# dianzicheng.net
KiCad netlist of a schematic drawn in Altium Designer
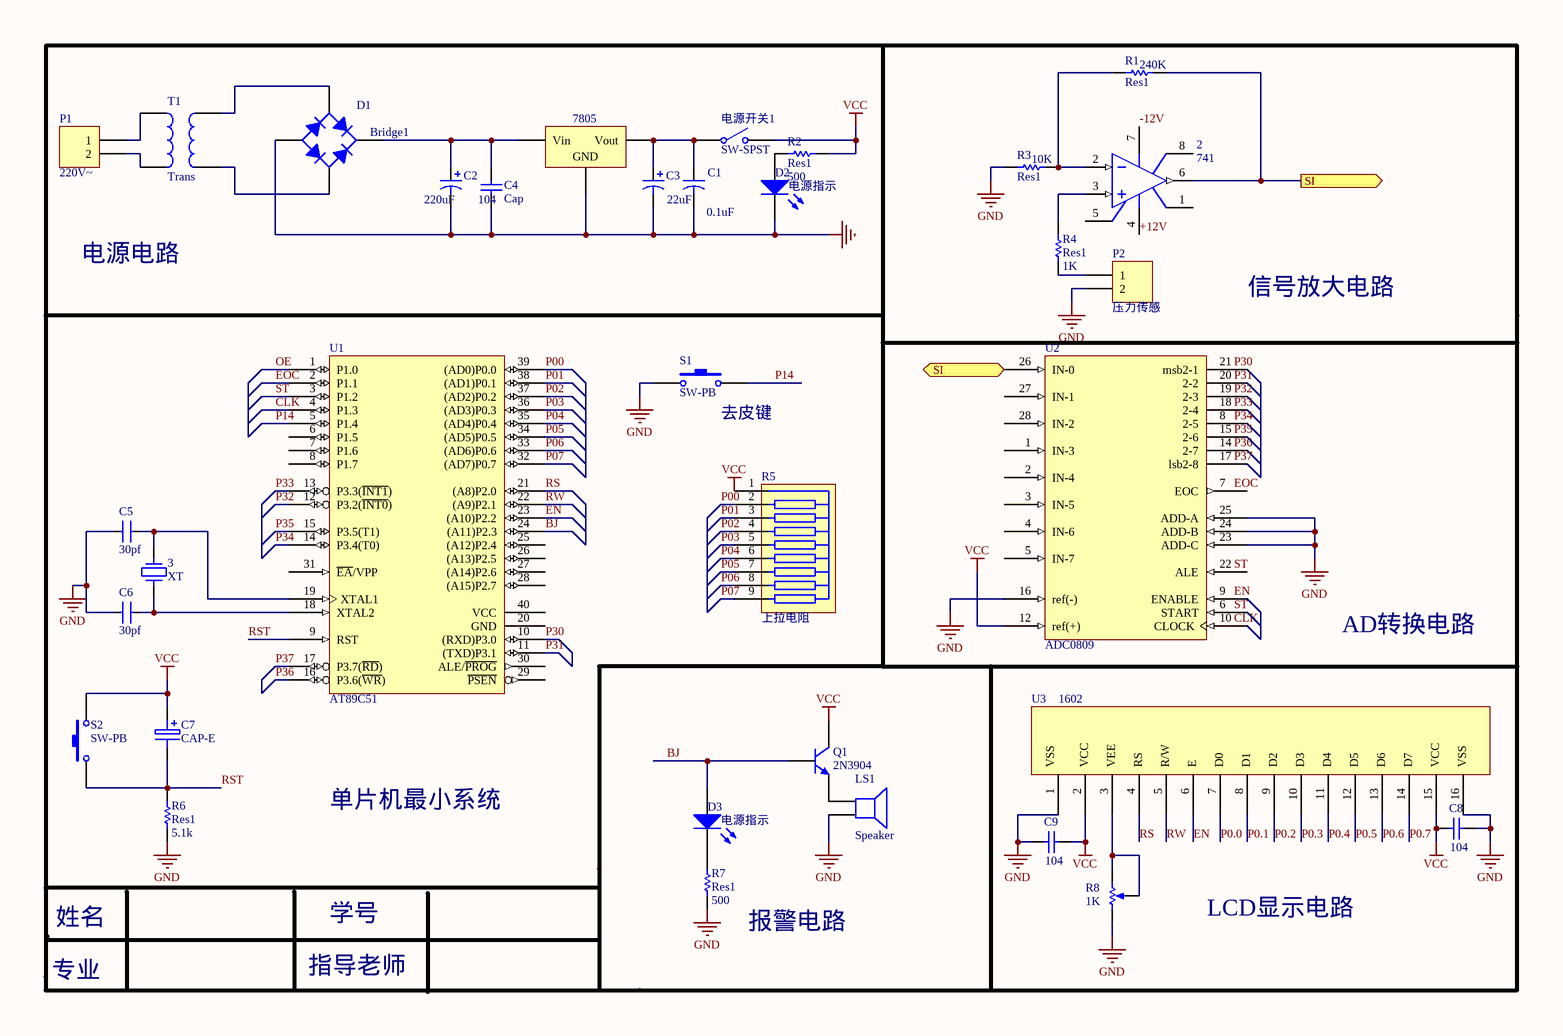
[diagram p0: dianzicheng.SchDoc]

(export (version "E")
  (design (tool "Eeschema 10.0.6"))
  (components
    (comp (ref "2")
      (value "741")
      (footprint "H-08A")
      (description "FET Operational Amplifier")
      (fields (field (name "PUBLISHER") "Altium Limited"))
      (libsource (lib "Miscellaneous Devices") (part "Op Amp"))
    )
    (comp (ref "3") (value "XT") (footprint "HC-49S") (description "晶振") (libsource (lib "常用器件") (part "XT")))
    (comp (ref "7805")
      (value "~")
      (footprint "SIP-G3/Y2")
      (description "Voltage Regulator")
      (fields (field (name "PUBLISHER") "Altium Limited"))
      (libsource (lib "Miscellaneous Devices") (part "Volt Reg"))
    )
    (comp (ref "C1")
      (value "0.1uF")
      (footprint "CAPR5-4X5")
      (description "Capacitor")
      (fields (field (name "PUBLISHER") "Altium Limited"))
      (libsource (lib "Miscellaneous Devices") (part "Cap2"))
    )
    (comp (ref "C2")
      (value "220uF")
      (footprint "CC2012-0805")
      (description "Polarized Capacitor (Surface Mount)")
      (fields (field (name "PUBLISHER") "Altium Limited"))
      (libsource (lib "Miscellaneous Devices") (part "Cap Pol3"))
    )
    (comp (ref "C3")
      (value "22uF")
      (footprint "CC2012-0805")
      (description "Polarized Capacitor (Surface Mount)")
      (fields (field (name "PUBLISHER") "Altium Limited"))
      (libsource (lib "Miscellaneous Devices") (part "Cap Pol3"))
    )
    (comp (ref "C4")
      (value "Cap")
      (footprint "RAD-0.3")
      (description "Capacitor")
      (fields (field (name "ALTIUM_VALUE") "104") (field (name "PUBLISHER") "Altium Limited"))
      (libsource (lib "Miscellaneous Devices") (part "Cap"))
    )
    (comp (ref "C5")
      (value "30pf")
      (footprint "0603C")
      (description "SMD-CAP")
      (libsource (lib "常用器件") (part "CAP-0.1UF"))
    )
    (comp (ref "C6")
      (value "30pf")
      (footprint "0603C")
      (description "SMD-CAP")
      (libsource (lib "常用器件") (part "CAP-0.1UF"))
    )
    (comp (ref "C7")
      (value "CAP-E")
      (footprint "RB.1/.3")
      (description "电解电容")
      (libsource (lib "常用器件") (part "CAP-E"))
    )
    (comp (ref "C8")
      (value "104")
      (footprint "RAD-0.3")
      (description "Capacitor")
      (fields (field (name "PUBLISHER") "Altium Limited"))
      (libsource (lib "Miscellaneous Devices") (part "Cap"))
    )
    (comp (ref "C9")
      (value "104")
      (footprint "RAD-0.3")
      (description "Capacitor")
      (fields (field (name "PUBLISHER") "Altium Limited"))
      (libsource (lib "Miscellaneous Devices") (part "Cap"))
    )
    (comp (ref "D1")
      (value "Bridge1")
      (footprint "D-38")
      (description "Full Wave Diode Bridge")
      (fields (field (name "PUBLISHER") "Altium Limited"))
      (libsource (lib "Miscellaneous Devices") (part "Bridge1"))
    )
    (comp (ref "D2")
      (value "电源指示")
      (footprint "DSO-F2/D6.1")
      (description "Typical RED, GREEN, YELLOW, AMBER GaAs LED")
      (fields (field (name "PUBLISHER") "Altium Limited"))
      (libsource (lib "Miscellaneous Devices") (part "LED2"))
    )
    (comp (ref "D3")
      (value "电源指示")
      (footprint "DSO-F2/D6.1")
      (description "Typical RED, GREEN, YELLOW, AMBER GaAs LED")
      (fields (field (name "PUBLISHER") "Altium Limited"))
      (libsource (lib "Miscellaneous Devices") (part "LED2"))
    )
    (comp (ref "LS1")
      (value "Speaker")
      (footprint "PIN2")
      (description "Loudspeaker")
      (fields (field (name "PUBLISHER") "Altium Limited"))
      (libsource (lib "Miscellaneous Devices") (part "Speaker"))
    )
    (comp (ref "P1")
      (value "220V~")
      (footprint "HDR1X2")
      (description "Header, 2-Pin")
      (fields (field (name "PUBLISHER") "Altium Limited"))
      (libsource (lib "") (part "Header 2_1"))
    )
    (comp (ref "P2")
      (value "压力传感")
      (footprint "HDR1X2")
      (description "Header, 2-Pin")
      (fields (field (name "PUBLISHER") "Altium Limited"))
      (libsource (lib "Miscellaneous Connectors") (part "Header 2"))
    )
    (comp (ref "Q1")
      (value "2N3904")
      (footprint "TO-92A")
      (description "NPN General Purpose Amplifier")
      (fields (field (name "PUBLISHER") "Altium Limited"))
      (libsource (lib "Miscellaneous Devices") (part "2N3904"))
    )
    (comp (ref "R1")
      (value "Res1")
      (footprint "AXIAL-0.3")
      (description "Resistor")
      (fields (field (name "ALTIUM_VALUE") "240K") (field (name "PUBLISHER") "Altium Limited"))
      (libsource (lib "Miscellaneous Devices") (part "Res1"))
    )
    (comp (ref "R2")
      (value "Res1")
      (footprint "AXIAL-0.3")
      (description "Resistor")
      (fields (field (name "ALTIUM_VALUE") "500") (field (name "PUBLISHER") "Altium Limited"))
      (libsource (lib "Miscellaneous Devices") (part "Res1"))
    )
    (comp (ref "R3")
      (value "Res1")
      (footprint "AXIAL-0.3")
      (description "Resistor")
      (fields (field (name "ALTIUM_VALUE") "10K") (field (name "PUBLISHER") "Altium Limited"))
      (libsource (lib "Miscellaneous Devices") (part "Res1"))
    )
    (comp (ref "R4")
      (value "Res1")
      (footprint "AXIAL-0.3")
      (description "Resistor")
      (fields (field (name "ALTIUM_VALUE") "1K") (field (name "PUBLISHER") "Altium Limited"))
      (libsource (lib "Miscellaneous Devices") (part "Res1"))
    )
    (comp (ref "R5") (value "上拉电阻") (footprint "sip9") (libsource (lib "R电阻") (part "排阻")))
    (comp (ref "R6")
      (value "Res1")
      (footprint "AXIAL-0.3")
      (description "Resistor")
      (fields (field (name "ALTIUM_VALUE") "5.1k") (field (name "PUBLISHER") "Altium Limited"))
      (libsource (lib "Miscellaneous Devices") (part "Res1"))
    )
    (comp (ref "R7")
      (value "Res1")
      (footprint "AXIAL-0.3")
      (description "Resistor")
      (fields (field (name "ALTIUM_VALUE") "500") (field (name "PUBLISHER") "Altium Limited"))
      (libsource (lib "Miscellaneous Devices") (part "Res1"))
    )
    (comp (ref "R8")
      (value "1K")
      (footprint "VR5")
      (description "Potentiometer")
      (fields (field (name "PUBLISHER") "Altium Limited"))
      (libsource (lib "Miscellaneous Devices") (part "RPot"))
    )
    (comp (ref "S1")
      (value "SW-PB")
      (footprint "SPST-2")
      (description "Switch")
      (fields (field (name "PUBLISHER") "Altium Limited"))
      (libsource (lib "常用器件") (part "SW-PB"))
    )
    (comp (ref "S2")
      (value "SW-PB")
      (footprint "SPST-2")
      (description "Switch")
      (fields (field (name "PUBLISHER") "Altium Limited"))
      (libsource (lib "常用器件") (part "SW-PB"))
    )
    (comp (ref "T1")
      (value "Trans")
      (footprint "TRANS")
      (description "Transformer")
      (fields (field (name "PUBLISHER") "Altium Limited"))
      (libsource (lib "Miscellaneous Devices") (part "Trans"))
    )
    (comp (ref "U1")
      (value "AT89C51")
      (footprint "DIP-40")
      (description "8-Bit Microcontroller with 4K Flash ROM")
      (libsource (lib "单片机8051") (part "AT89C51"))
    )
    (comp (ref "U2") (value "ADC0809") (footprint "DIP28") (libsource (lib "单片机及相关") (part "ADC0809")))
    (comp (ref "U3") (value "1602") (libsource (lib "signal general") (part "1602")))
    (comp (ref "电源开关1")
      (value "SW-SPST")
      (footprint "SPST-2")
      (description "Single-Pole, Single-Throw Switch")
      (fields (field (name "PUBLISHER") "Altium Limited"))
      (libsource (lib "Miscellaneous Devices") (part "SW-SPST"))
    )
  )
  (nets
    (net (code "1") (name "/+12V") (class "Default")
      (node (ref "2") (pin "4") (pinfunction "V-_4") (pintype "power_in"))
    )
    (net (code "2") (name "/-12V") (class "Default")
      (node (ref "2") (pin "7") (pinfunction "V+_7") (pintype "power_in"))
    )
    (net (code "3") (name "/BJ") (class "Default")
      (node (ref "D3") (pin "1") (pinfunction "A_1") (pintype "passive"))
      (node (ref "Q1") (pin "2") (pinfunction "B_2") (pintype "passive"))
      (node (ref "U1") (pin "24") (pinfunction "(A11)P2.3_24") (pintype "bidirectional"))
    )
    (net (code "4") (name "/CLK") (class "Default")
      (node (ref "U1") (pin "4") (pinfunction "P1.3_4") (pintype "bidirectional"))
    )
    (net (code "5") (name "/EN") (class "Default")
      (node (ref "U1") (pin "23") (pinfunction "(A10)P2.2_23") (pintype "bidirectional"))
      (node (ref "U3") (pin "6") (pintype "passive"))
    )
    (net (code "6") (name "/EOC") (class "Default")
      (node (ref "U1") (pin "2") (pinfunction "P1.1_2") (pintype "bidirectional"))
    )
    (net (code "7") (name "/OE") (class "Default")
      (node (ref "U1") (pin "1") (pinfunction "P1.0_1") (pintype "bidirectional"))
    )
    (net (code "8") (name "/P00") (class "Default")
      (node (ref "R5") (pin "2") (pinfunction "2_2") (pintype "passive"))
      (node (ref "U1") (pin "39") (pinfunction "(AD0)P0.0_39") (pintype "bidirectional"))
    )
    (net (code "9") (name "/P0.0") (class "Default") (node (ref "U3") (pin "7") (pintype "passive")))
    (net (code "10") (name "/P0.1") (class "Default") (node (ref "U3") (pin "8") (pintype "passive")))
    (net (code "11") (name "/P0.2") (class "Default") (node (ref "U3") (pin "9") (pintype "passive")))
    (net (code "12") (name "/P0.3") (class "Default") (node (ref "U3") (pin "10") (pintype "passive")))
    (net (code "13") (name "/P0.4") (class "Default") (node (ref "U3") (pin "11") (pintype "passive")))
    (net (code "14") (name "/P0.5") (class "Default") (node (ref "U3") (pin "12") (pintype "passive")))
    (net (code "15") (name "/P0.6") (class "Default") (node (ref "U3") (pin "13") (pintype "passive")))
    (net (code "16") (name "/P0.7") (class "Default") (node (ref "U3") (pin "14") (pintype "passive")))
    (net (code "17") (name "/P01") (class "Default")
      (node (ref "R5") (pin "3") (pinfunction "3_3") (pintype "passive"))
      (node (ref "U1") (pin "38") (pinfunction "(AD1)P0.1_38") (pintype "bidirectional"))
    )
    (net (code "18") (name "/P02") (class "Default")
      (node (ref "R5") (pin "4") (pinfunction "4_4") (pintype "passive"))
      (node (ref "U1") (pin "37") (pinfunction "(AD2)P0.2_37") (pintype "bidirectional"))
    )
    (net (code "19") (name "/P03") (class "Default")
      (node (ref "R5") (pin "5") (pinfunction "5_5") (pintype "passive"))
      (node (ref "U1") (pin "36") (pinfunction "(AD3)P0.3_36") (pintype "bidirectional"))
    )
    (net (code "20") (name "/P04") (class "Default")
      (node (ref "R5") (pin "6") (pinfunction "6_6") (pintype "passive"))
      (node (ref "U1") (pin "35") (pinfunction "(AD4)P0.4_35") (pintype "bidirectional"))
    )
    (net (code "21") (name "/P05") (class "Default")
      (node (ref "R5") (pin "7") (pinfunction "7_7") (pintype "passive"))
      (node (ref "U1") (pin "34") (pinfunction "(AD5)P0.5_34") (pintype "bidirectional"))
    )
    (net (code "22") (name "/P06") (class "Default")
      (node (ref "R5") (pin "8") (pinfunction "8_8") (pintype "passive"))
      (node (ref "U1") (pin "33") (pinfunction "(AD6)P0.6_33") (pintype "bidirectional"))
    )
    (net (code "23") (name "/P07") (class "Default")
      (node (ref "R5") (pin "9") (pinfunction "9_9") (pintype "passive"))
      (node (ref "U1") (pin "32") (pinfunction "(AD7)P0.7_32") (pintype "bidirectional"))
    )
    (net (code "24") (name "/P14") (class "Default")
      (node (ref "S1") (pin "2") (pinfunction "2_2") (pintype "passive"))
      (node (ref "U1") (pin "5") (pinfunction "P1.4_5") (pintype "bidirectional"))
    )
    (net (code "25") (name "/P30") (class "Default")
      (node (ref "U1") (pin "10") (pinfunction "(RXD)P3.0_10") (pintype "bidirectional"))
    )
    (net (code "26") (name "/P31") (class "Default")
      (node (ref "U1") (pin "11") (pinfunction "(TXD)P3.1_11") (pintype "bidirectional"))
    )
    (net (code "27") (name "/P32") (class "Default")
      (node (ref "U1") (pin "12") (pinfunction "P3.2(~{INT0})_12") (pintype "bidirectional"))
    )
    (net (code "28") (name "/P33") (class "Default")
      (node (ref "U1") (pin "13") (pinfunction "P3.3(~{INT1})_13") (pintype "bidirectional"))
    )
    (net (code "29") (name "/P34") (class "Default")
      (node (ref "U1") (pin "14") (pinfunction "P3.4(T0)_14") (pintype "bidirectional"))
    )
    (net (code "30") (name "/P35") (class "Default")
      (node (ref "U1") (pin "15") (pinfunction "P3.5(T1)_15") (pintype "bidirectional"))
    )
    (net (code "31") (name "/P36") (class "Default")
      (node (ref "U1") (pin "16") (pinfunction "P3.6(~{WR})_16") (pintype "bidirectional"))
    )
    (net (code "32") (name "/P37") (class "Default")
      (node (ref "U1") (pin "17") (pinfunction "P3.7(~{RD})_17") (pintype "bidirectional"))
    )
    (net (code "33") (name "/RS") (class "Default")
      (node (ref "U1") (pin "21") (pinfunction "(A8)P2.0_21") (pintype "bidirectional"))
      (node (ref "U3") (pin "4") (pintype "passive"))
    )
    (net (code "34") (name "/RST") (class "Default")
      (node (ref "C7") (pin "2") (pinfunction "2_2") (pintype "passive"))
      (node (ref "R6") (pin "2") (pinfunction "2_2") (pintype "passive"))
      (node (ref "S2") (pin "1") (pinfunction "1_1") (pintype "passive"))
      (node (ref "U1") (pin "9") (pinfunction "RST_9") (pintype "input"))
    )
    (net (code "35") (name "/RW") (class "Default")
      (node (ref "U1") (pin "22") (pinfunction "(A9)P2.1_22") (pintype "bidirectional"))
      (node (ref "U3") (pin "5") (pintype "passive"))
    )
    (net (code "36") (name "/SI") (class "Default")
      (node (ref "2") (pin "6") (pinfunction "OUT_6") (pintype "output"))
      (node (ref "R1") (pin "2") (pinfunction "2_2") (pintype "passive"))
      (node (ref "U2") (pin "26") (pinfunction "IN-0_26") (pintype "input"))
    )
    (net (code "37") (name "/ST") (class "Default")
      (node (ref "U1") (pin "3") (pinfunction "P1.2_3") (pintype "bidirectional"))
    )
    (net (code "38") (name "GND") (class "Default")
      (node (ref "7805") (pin "2") (pinfunction "GND_2") (pintype "passive"))
      (node (ref "C1") (pin "2") (pinfunction "2_2") (pintype "passive"))
      (node (ref "C2") (pin "2") (pinfunction "2_2") (pintype "passive"))
      (node (ref "C3") (pin "2") (pinfunction "2_2") (pintype "passive"))
      (node (ref "C4") (pin "1") (pinfunction "1_1") (pintype "passive"))
      (node (ref "C5") (pin "2") (pinfunction "2_2") (pintype "passive"))
      (node (ref "C6") (pin "2") (pinfunction "2_2") (pintype "passive"))
      (node (ref "C8") (pin "2") (pinfunction "2_2") (pintype "passive"))
      (node (ref "C9") (pin "1") (pinfunction "1_1") (pintype "passive"))
      (node (ref "D1") (pin "3") (pinfunction "A_3") (pintype "passive"))
      (node (ref "D2") (pin "2") (pinfunction "K_2") (pintype "passive"))
      (node (ref "LS1") (pin "2") (pinfunction "2_2") (pintype "passive"))
      (node (ref "P2") (pin "2") (pinfunction "2_2") (pintype "passive"))
      (node (ref "R3") (pin "1") (pinfunction "1_1") (pintype "passive"))
      (node (ref "R6") (pin "1") (pinfunction "1_1") (pintype "passive"))
      (node (ref "R7") (pin "1") (pinfunction "1_1") (pintype "passive"))
      (node (ref "R8") (pin "1") (pinfunction "TOP_1") (pintype "passive"))
      (node (ref "S1") (pin "1") (pinfunction "1_1") (pintype "passive"))
      (node (ref "U2") (pin "13") (pinfunction "GND_13") (pintype "power_in"))
      (node (ref "U2") (pin "16") (pinfunction "ref(-)_16") (pintype "input"))
      (node (ref "U2") (pin "23") (pinfunction "ADD-C_23") (pintype "input"))
      (node (ref "U2") (pin "24") (pinfunction "ADD-B_24") (pintype "input"))
      (node (ref "U2") (pin "25") (pinfunction "ADD-A_25") (pintype "input"))
      (node (ref "U3") (pin "1") (pintype "passive"))
      (node (ref "U3") (pin "16") (pintype "passive"))
    )
    (net (code "39") (name "Net-(2-IN+)") (class "Default")
      (node (ref "2") (pin "3") (pinfunction "IN+_3") (pintype "input"))
      (node (ref "R4") (pin "2") (pinfunction "2_2") (pintype "passive"))
    )
    (net (code "40") (name "Net-(2-IN-)") (class "Default")
      (node (ref "2") (pin "2") (pinfunction "IN-_2") (pintype "input"))
      (node (ref "R1") (pin "1") (pinfunction "1_1") (pintype "passive"))
      (node (ref "R3") (pin "2") (pinfunction "2_2") (pintype "passive"))
    )
    (net (code "41") (name "Net-(7805-Vin)") (class "Default")
      (node (ref "7805") (pin "1") (pinfunction "Vin_1") (pintype "passive"))
      (node (ref "C2") (pin "1") (pinfunction "1_1") (pintype "passive"))
      (node (ref "C4") (pin "2") (pinfunction "2_2") (pintype "passive"))
      (node (ref "D1") (pin "1") (pinfunction "K_1") (pintype "passive"))
    )
    (net (code "42") (name "Net-(7805-Vout)") (class "Default")
      (node (ref "7805") (pin "3") (pinfunction "Vout_3") (pintype "passive"))
      (node (ref "C1") (pin "1") (pinfunction "1_1") (pintype "passive"))
      (node (ref "C3") (pin "1") (pinfunction "1_1") (pintype "passive"))
      (node (ref "电源开关1") (pin "1") (pinfunction "COMMON_1") (pintype "passive"))
    )
    (net (code "43") (name "Net-(D1-C-Pad2)") (class "Default")
      (node (ref "D1") (pin "2") (pinfunction "C_2") (pintype "passive"))
      (node (ref "T1") (pin "4") (pinfunction "4_4") (pintype "passive"))
    )
    (net (code "44") (name "Net-(D1-C-Pad4)") (class "Default")
      (node (ref "D1") (pin "4") (pinfunction "C_4") (pintype "passive"))
      (node (ref "T1") (pin "3") (pinfunction "3_3") (pintype "passive"))
    )
    (net (code "45") (name "Net-(D2-A)") (class "Default")
      (node (ref "D2") (pin "1") (pinfunction "A_1") (pintype "passive"))
      (node (ref "R2") (pin "2") (pinfunction "2_2") (pintype "passive"))
    )
    (net (code "46") (name "Net-(D3-K)") (class "Default")
      (node (ref "D3") (pin "2") (pinfunction "K_2") (pintype "passive"))
      (node (ref "R7") (pin "2") (pinfunction "2_2") (pintype "passive"))
    )
    (net (code "47") (name "Net-(P1-Pad1)") (class "Default")
      (node (ref "P1") (pin "1") (pinfunction "1_1") (pintype "passive"))
      (node (ref "T1") (pin "1") (pinfunction "1_1") (pintype "passive"))
    )
    (net (code "48") (name "Net-(P1-Pad2)") (class "Default")
      (node (ref "P1") (pin "2") (pinfunction "2_2") (pintype "passive"))
      (node (ref "T1") (pin "2") (pinfunction "2_2") (pintype "passive"))
    )
    (net (code "49") (name "Net-(P2-Pad1)") (class "Default")
      (node (ref "P2") (pin "1") (pinfunction "1_1") (pintype "passive"))
      (node (ref "R4") (pin "1") (pinfunction "1_1") (pintype "passive"))
    )
    (net (code "50") (name "Net-(Q1-E)") (class "Default")
      (node (ref "LS1") (pin "1") (pinfunction "1_1") (pintype "passive"))
      (node (ref "Q1") (pin "1") (pinfunction "E_1") (pintype "passive"))
    )
    (net (code "51") (name "Net-(R8-BOT)") (class "Default")
      (node (ref "R8") (pin "2") (pinfunction "BOT_2") (pintype "passive"))
      (node (ref "R8") (pin "3") (pinfunction "TAP_3") (pintype "passive"))
      (node (ref "U3") (pin "3") (pintype "passive"))
    )
    (net (code "52") (name "Net-(U1-XTAL1)") (class "Default")
      (node (ref "3") (pin "2") (pinfunction "2_2") (pintype "passive"))
      (node (ref "C5") (pin "1") (pinfunction "1_1") (pintype "passive"))
      (node (ref "U1") (pin "19") (pinfunction "XTAL1_19") (pintype "input"))
    )
    (net (code "53") (name "Net-(U1-XTAL2)") (class "Default")
      (node (ref "3") (pin "1") (pinfunction "1_1") (pintype "passive"))
      (node (ref "C6") (pin "1") (pinfunction "1_1") (pintype "passive"))
      (node (ref "U1") (pin "18") (pinfunction "XTAL2_18") (pintype "input"))
    )
    (net (code "54") (name "VCC") (class "Default")
      (node (ref "C7") (pin "1") (pinfunction "1_1") (pintype "passive"))
      (node (ref "C8") (pin "1") (pinfunction "1_1") (pintype "passive"))
      (node (ref "C9") (pin "2") (pinfunction "2_2") (pintype "passive"))
      (node (ref "Q1") (pin "3") (pinfunction "C_3") (pintype "passive"))
      (node (ref "R2") (pin "1") (pinfunction "1_1") (pintype "passive"))
      (node (ref "R5") (pin "1") (pinfunction "1_1") (pintype "passive"))
      (node (ref "S2") (pin "2") (pinfunction "2_2") (pintype "passive"))
      (node (ref "U2") (pin "12") (pinfunction "ref(+)_12") (pintype "input"))
      (node (ref "U3") (pin "15") (pintype "passive"))
      (node (ref "U3") (pin "2") (pintype "passive"))
      (node (ref "电源开关1") (pin "2") (pinfunction "NO_2") (pintype "passive"))
    )
    (net (code "55") (name "unconnected-(2-OS_NUL-Pad1)") (class "Default")
      (node (ref "2") (pin "1") (pinfunction "OS_NUL_1") (pintype "passive"))
    )
    (net (code "56") (name "unconnected-(2-OS_NUL-Pad5)") (class "Default")
      (node (ref "2") (pin "5") (pinfunction "OS_NUL_5") (pintype "passive"))
    )
    (net (code "57") (name "unconnected-(2-TAB-Pad8)") (class "Default")
      (node (ref "2") (pin "8") (pinfunction "TAB_8") (pintype "passive"))
    )
    (net (code "58") (name "unconnected-(U1-(A12)P2.4-Pad25)") (class "Default")
      (node (ref "U1") (pin "25") (pinfunction "(A12)P2.4_25") (pintype "bidirectional"))
    )
    (net (code "59") (name "unconnected-(U1-(A13)P2.5-Pad26)") (class "Default")
      (node (ref "U1") (pin "26") (pinfunction "(A13)P2.5_26") (pintype "bidirectional"))
    )
    (net (code "60") (name "unconnected-(U1-(A14)P2.6-Pad27)") (class "Default")
      (node (ref "U1") (pin "27") (pinfunction "(A14)P2.6_27") (pintype "bidirectional"))
    )
    (net (code "61") (name "unconnected-(U1-(A15)P2.7-Pad28)") (class "Default")
      (node (ref "U1") (pin "28") (pinfunction "(A15)P2.7_28") (pintype "bidirectional"))
    )
    (net (code "62") (name "unconnected-(U1-ALE{slash}~{PROG}-Pad30)") (class "Default")
      (node (ref "U1") (pin "30") (pinfunction "ALE/~{PROG}_30") (pintype "output"))
    )
    (net (code "63") (name "unconnected-(U1-GND-Pad20)") (class "Default")
      (node (ref "U1") (pin "20") (pinfunction "GND_20") (pintype "power_in"))
    )
    (net (code "64") (name "unconnected-(U1-P1.5-Pad6)") (class "Default")
      (node (ref "U1") (pin "6") (pinfunction "P1.5_6") (pintype "bidirectional"))
    )
    (net (code "65") (name "unconnected-(U1-P1.6-Pad7)") (class "Default")
      (node (ref "U1") (pin "7") (pinfunction "P1.6_7") (pintype "bidirectional"))
    )
    (net (code "66") (name "unconnected-(U1-P1.7-Pad8)") (class "Default")
      (node (ref "U1") (pin "8") (pinfunction "P1.7_8") (pintype "bidirectional"))
    )
    (net (code "67") (name "unconnected-(U1-VCC-Pad40)") (class "Default")
      (node (ref "U1") (pin "40") (pinfunction "VCC_40") (pintype "power_in"))
    )
    (net (code "68") (name "unconnected-(U1-~{EA}{slash}VPP-Pad31)") (class "Default")
      (node (ref "U1") (pin "31") (pinfunction "~{EA}/VPP_31") (pintype "input"))
    )
    (net (code "69") (name "unconnected-(U1-~{PSEN}-Pad29)") (class "Default")
      (node (ref "U1") (pin "29") (pinfunction "~{PSEN}_29") (pintype "output"))
    )
    (net (code "70") (name "unconnected-(U2-2-2-Pad20)") (class "Default")
      (node (ref "U2") (pin "20") (pinfunction "2-2_20") (pintype "tri_state"))
    )
    (net (code "71") (name "unconnected-(U2-2-3-Pad19)") (class "Default")
      (node (ref "U2") (pin "19") (pinfunction "2-3_19") (pintype "tri_state"))
    )
    (net (code "72") (name "unconnected-(U2-2-4-Pad18)") (class "Default")
      (node (ref "U2") (pin "18") (pinfunction "2-4_18") (pintype "tri_state"))
    )
    (net (code "73") (name "unconnected-(U2-2-5-Pad8)") (class "Default")
      (node (ref "U2") (pin "8") (pinfunction "2-5_8") (pintype "tri_state"))
    )
    (net (code "74") (name "unconnected-(U2-2-6-Pad15)") (class "Default")
      (node (ref "U2") (pin "15") (pinfunction "2-6_15") (pintype "tri_state"))
    )
    (net (code "75") (name "unconnected-(U2-2-7-Pad14)") (class "Default")
      (node (ref "U2") (pin "14") (pinfunction "2-7_14") (pintype "tri_state"))
    )
    (net (code "76") (name "unconnected-(U2-ALE-Pad22)") (class "Default")
      (node (ref "U2") (pin "22") (pinfunction "ALE_22") (pintype "input"))
    )
    (net (code "77") (name "unconnected-(U2-CLOCK-Pad10)") (class "Default")
      (node (ref "U2") (pin "10") (pinfunction "CLOCK_10") (pintype "input"))
    )
    (net (code "78") (name "unconnected-(U2-ENABLE-Pad9)") (class "Default")
      (node (ref "U2") (pin "9") (pinfunction "ENABLE_9") (pintype "input"))
    )
    (net (code "79") (name "unconnected-(U2-EOC-Pad7)") (class "Default")
      (node (ref "U2") (pin "7") (pinfunction "EOC_7") (pintype "output"))
    )
    (net (code "80") (name "unconnected-(U2-IN-1-Pad27)") (class "Default")
      (node (ref "U2") (pin "27") (pinfunction "IN-1_27") (pintype "input"))
    )
    (net (code "81") (name "unconnected-(U2-IN-2-Pad28)") (class "Default")
      (node (ref "U2") (pin "28") (pinfunction "IN-2_28") (pintype "input"))
    )
    (net (code "82") (name "unconnected-(U2-IN-3-Pad1)") (class "Default")
      (node (ref "U2") (pin "1") (pinfunction "IN-3_1") (pintype "input"))
    )
    (net (code "83") (name "unconnected-(U2-IN-4-Pad2)") (class "Default")
      (node (ref "U2") (pin "2") (pinfunction "IN-4_2") (pintype "input"))
    )
    (net (code "84") (name "unconnected-(U2-IN-5-Pad3)") (class "Default")
      (node (ref "U2") (pin "3") (pinfunction "IN-5_3") (pintype "input"))
    )
    (net (code "85") (name "unconnected-(U2-IN-6-Pad4)") (class "Default")
      (node (ref "U2") (pin "4") (pinfunction "IN-6_4") (pintype "input"))
    )
    (net (code "86") (name "unconnected-(U2-IN-7-Pad5)") (class "Default")
      (node (ref "U2") (pin "5") (pinfunction "IN-7_5") (pintype "input"))
    )
    (net (code "87") (name "unconnected-(U2-START-Pad6)") (class "Default")
      (node (ref "U2") (pin "6") (pinfunction "START_6") (pintype "input"))
    )
    (net (code "88") (name "unconnected-(U2-lsb2-8-Pad17)") (class "Default")
      (node (ref "U2") (pin "17") (pinfunction "lsb2-8_17") (pintype "tri_state"))
    )
    (net (code "89") (name "unconnected-(U2-msb2-1-Pad21)") (class "Default")
      (node (ref "U2") (pin "21") (pinfunction "msb2-1_21") (pintype "tri_state"))
    )
  )
)
